# T4p1.net
KiCad netlist of a schematic drawn in EAGLE
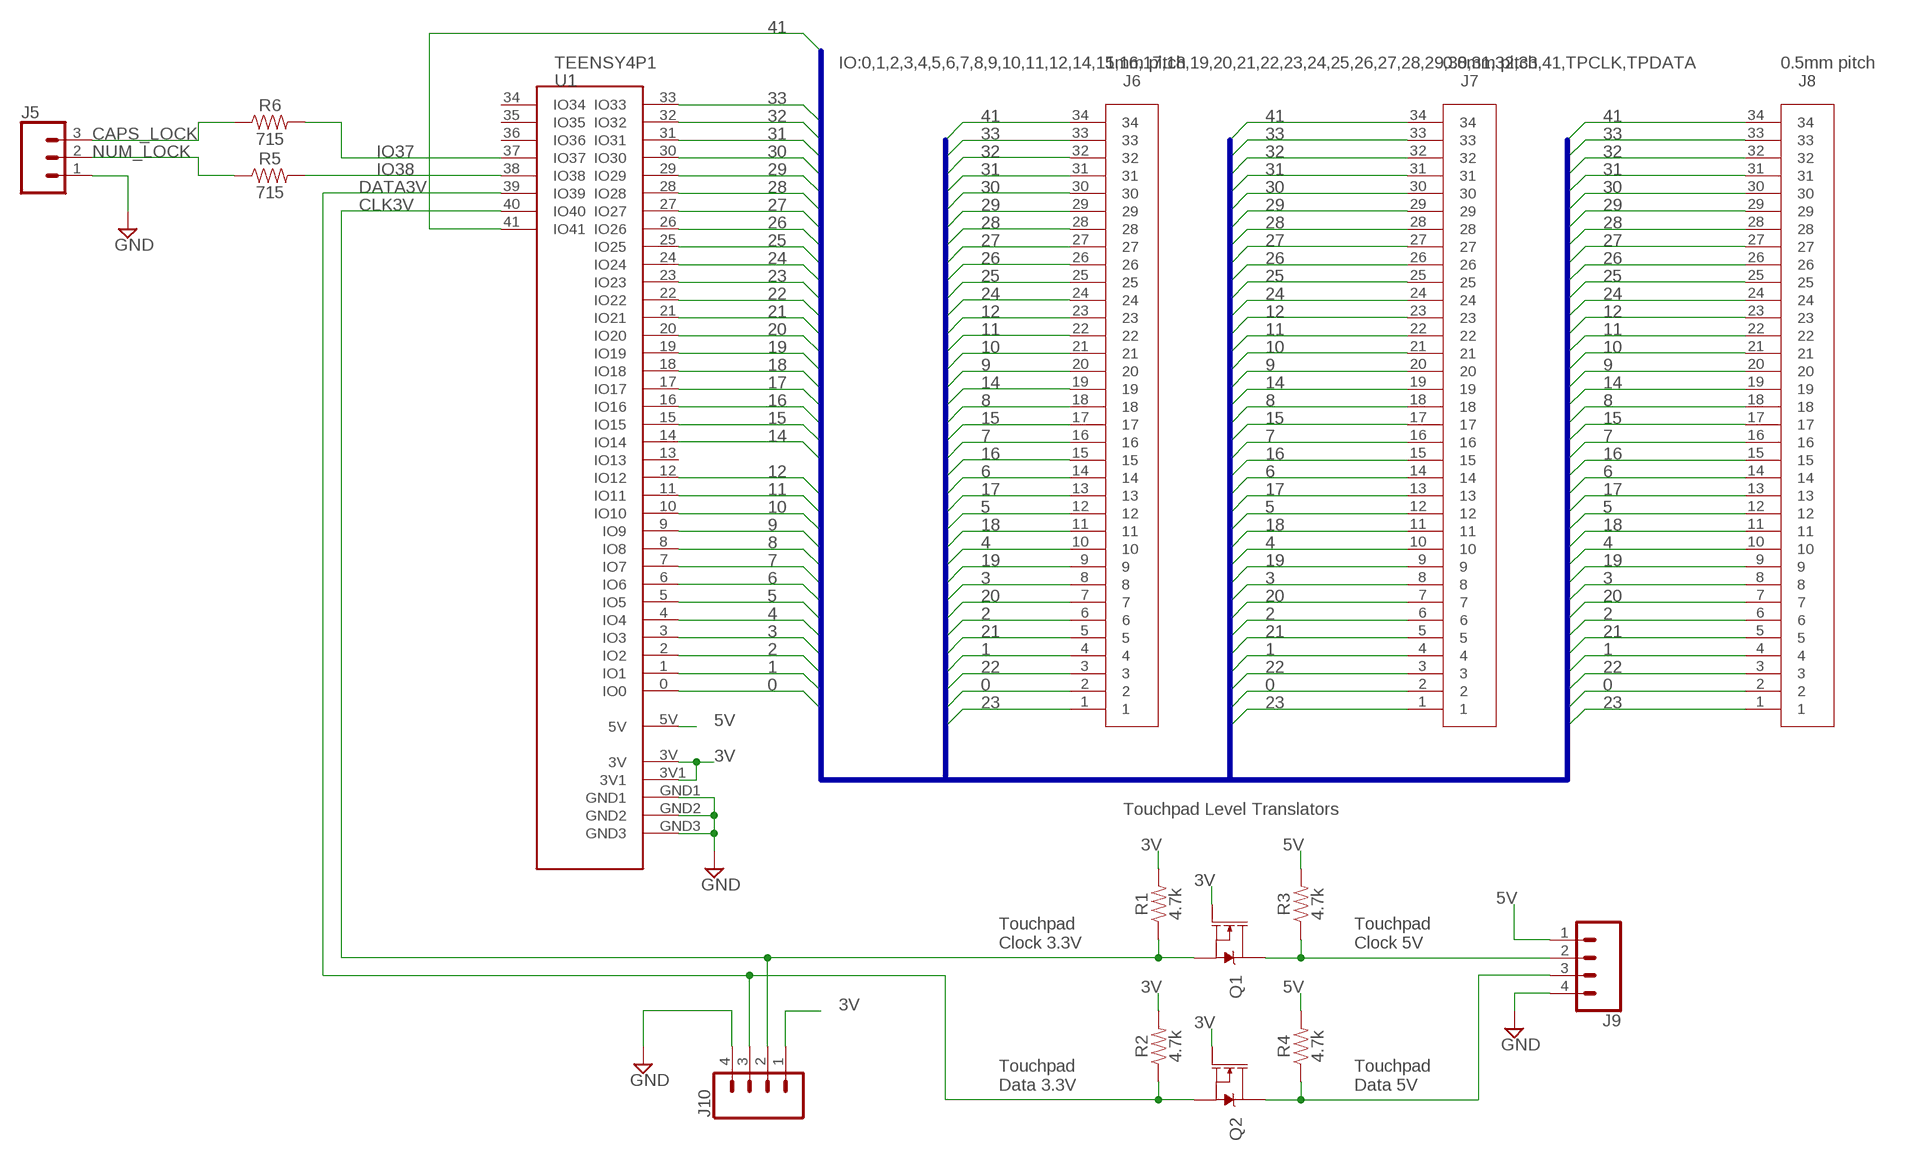
[diagram p0: schematic, sheet 1]

(export (version "E")
  (design (tool "Eeschema 10.0.6"))
  (components
    (comp (ref "J5")
      (value "CONN_031X03_NO_SILK")
      (footprint "eagle-import:1X03_NO_SILK")
      (libsource (lib "eagle-import") (part "CONN_031X03_NO_SILK"))
    )
    (comp (ref "J6")
      (value "FPC34")
      (footprint "eagle-import:FPC34")
      (libsource (lib "eagle-import") (part "FPC34"))
    )
    (comp (ref "J7")
      (value "FPC34_P8MM")
      (footprint "eagle-import:FPC34_P8MM")
      (libsource (lib "eagle-import") (part "FPC34_P8MM"))
    )
    (comp (ref "J8")
      (value "FPC34_P5MM")
      (footprint "eagle-import:FPC34_P5MM")
      (libsource (lib "eagle-import") (part "FPC34_P5MM"))
    )
    (comp (ref "J9")
      (value "CONN_041X04_NO_SILK")
      (footprint "eagle-import:1X04_NO_SILK")
      (libsource (lib "eagle-import") (part "CONN_041X04_NO_SILK"))
    )
    (comp (ref "J10")
      (value "CONN_041X04_NO_SILK")
      (footprint "eagle-import:1X04_NO_SILK")
      (libsource (lib "eagle-import") (part "CONN_041X04_NO_SILK"))
    )
    (comp (ref "Q1")
      (value "220mA/50V/3.5Ω")
      (footprint "eagle-import:SOT23-3")
      (libsource (lib "eagle-import") (part "MOSFET-NCH-BSS138"))
    )
    (comp (ref "Q2")
      (value "220mA/50V/3.5Ω")
      (footprint "eagle-import:SOT23-3")
      (libsource (lib "eagle-import") (part "MOSFET-NCH-BSS138"))
    )
    (comp (ref "R1")
      (value "4.7k")
      (footprint "eagle-import:0603")
      (libsource (lib "eagle-import") (part "4.7KOHM-0603-1/10W-1%"))
    )
    (comp (ref "R2")
      (value "4.7k")
      (footprint "eagle-import:0603")
      (libsource (lib "eagle-import") (part "4.7KOHM-0603-1/10W-1%"))
    )
    (comp (ref "R3")
      (value "4.7k")
      (footprint "eagle-import:0603")
      (libsource (lib "eagle-import") (part "4.7KOHM-0603-1/10W-1%"))
    )
    (comp (ref "R4")
      (value "4.7k")
      (footprint "eagle-import:0603")
      (libsource (lib "eagle-import") (part "4.7KOHM-0603-1/10W-1%"))
    )
    (comp (ref "R5")
      (value "715")
      (footprint "eagle-import:0603")
      (libsource (lib "eagle-import") (part "715OHM-0603-1/10W-1%"))
    )
    (comp (ref "R6")
      (value "715")
      (footprint "eagle-import:0603")
      (libsource (lib "eagle-import") (part "715OHM-0603-1/10W-1%"))
    )
    (comp (ref "U1")
      (value "TEENSY4P1")
      (footprint "eagle-import:TEENSY4P1")
      (libsource (lib "eagle-import") (part "TEENSYP41"))
    )
  )
  (nets
    (net (code "4") (name "/0") (class "Default")
      (node (ref "J6") (pin "2") (pinfunction "2_2") (pintype "bidirectional"))
      (node (ref "J7") (pin "2") (pinfunction "2_2") (pintype "bidirectional"))
      (node (ref "J8") (pin "2") (pinfunction "2_2") (pintype "bidirectional"))
      (node (ref "U1") (pin "0") (pinfunction "IO0_0") (pintype "bidirectional"))
    )
    (net (code "5") (name "/1") (class "Default")
      (node (ref "J6") (pin "4") (pinfunction "4_4") (pintype "bidirectional"))
      (node (ref "J7") (pin "4") (pinfunction "4_4") (pintype "bidirectional"))
      (node (ref "J8") (pin "4") (pinfunction "4_4") (pintype "bidirectional"))
      (node (ref "U1") (pin "1") (pinfunction "IO1_1") (pintype "bidirectional"))
    )
    (net (code "6") (name "/2") (class "Default")
      (node (ref "J6") (pin "6") (pinfunction "6_6") (pintype "bidirectional"))
      (node (ref "J7") (pin "6") (pinfunction "6_6") (pintype "bidirectional"))
      (node (ref "J8") (pin "6") (pinfunction "6_6") (pintype "bidirectional"))
      (node (ref "U1") (pin "2") (pinfunction "IO2_2") (pintype "bidirectional"))
    )
    (net (code "7") (name "/3") (class "Default")
      (node (ref "J6") (pin "8") (pinfunction "8_8") (pintype "bidirectional"))
      (node (ref "J7") (pin "8") (pinfunction "8_8") (pintype "bidirectional"))
      (node (ref "J8") (pin "8") (pinfunction "8_8") (pintype "bidirectional"))
      (node (ref "U1") (pin "3") (pinfunction "IO3_3") (pintype "bidirectional"))
    )
    (net (code "8") (name "/3V") (class "Default")
      (node (ref "J10") (pin "1") (pinfunction "1_1") (pintype "passive"))
      (node (ref "Q1") (pin "1") (pinfunction "G_1") (pintype "bidirectional"))
      (node (ref "Q2") (pin "1") (pinfunction "G_1") (pintype "bidirectional"))
      (node (ref "R1") (pin "2") (pinfunction "2_2") (pintype "passive"))
      (node (ref "R2") (pin "2") (pinfunction "2_2") (pintype "passive"))
      (node (ref "U1") (pin "3V") (pinfunction "3V_3V") (pintype "bidirectional"))
      (node (ref "U1") (pin "3V1") (pinfunction "3V1_3V1") (pintype "bidirectional"))
    )
    (net (code "9") (name "/4") (class "Default")
      (node (ref "J6") (pin "10") (pinfunction "10_10") (pintype "bidirectional"))
      (node (ref "J7") (pin "10") (pinfunction "10_10") (pintype "bidirectional"))
      (node (ref "J8") (pin "10") (pinfunction "10_10") (pintype "bidirectional"))
      (node (ref "U1") (pin "4") (pinfunction "IO4_4") (pintype "bidirectional"))
    )
    (net (code "10") (name "/5") (class "Default")
      (node (ref "J6") (pin "12") (pinfunction "12_12") (pintype "bidirectional"))
      (node (ref "J7") (pin "12") (pinfunction "12_12") (pintype "bidirectional"))
      (node (ref "J8") (pin "12") (pinfunction "12_12") (pintype "bidirectional"))
      (node (ref "U1") (pin "5") (pinfunction "IO5_5") (pintype "bidirectional"))
    )
    (net (code "11") (name "/5V") (class "Default")
      (node (ref "J9") (pin "1") (pinfunction "1_1") (pintype "passive"))
      (node (ref "R3") (pin "2") (pinfunction "2_2") (pintype "passive"))
      (node (ref "R4") (pin "2") (pinfunction "2_2") (pintype "passive"))
      (node (ref "U1") (pin "5V") (pinfunction "5V_5V") (pintype "bidirectional"))
    )
    (net (code "12") (name "/6") (class "Default")
      (node (ref "J6") (pin "14") (pinfunction "14_14") (pintype "bidirectional"))
      (node (ref "J7") (pin "14") (pinfunction "14_14") (pintype "bidirectional"))
      (node (ref "J8") (pin "14") (pinfunction "14_14") (pintype "bidirectional"))
      (node (ref "U1") (pin "6") (pinfunction "IO6_6") (pintype "bidirectional"))
    )
    (net (code "13") (name "/7") (class "Default")
      (node (ref "J6") (pin "16") (pinfunction "16_16") (pintype "bidirectional"))
      (node (ref "J7") (pin "16") (pinfunction "16_16") (pintype "bidirectional"))
      (node (ref "J8") (pin "16") (pinfunction "16_16") (pintype "bidirectional"))
      (node (ref "U1") (pin "7") (pinfunction "IO7_7") (pintype "bidirectional"))
    )
    (net (code "14") (name "/8") (class "Default")
      (node (ref "J6") (pin "18") (pinfunction "18_18") (pintype "bidirectional"))
      (node (ref "J7") (pin "18") (pinfunction "18_18") (pintype "bidirectional"))
      (node (ref "J8") (pin "18") (pinfunction "18_18") (pintype "bidirectional"))
      (node (ref "U1") (pin "8") (pinfunction "IO8_8") (pintype "bidirectional"))
    )
    (net (code "15") (name "/9") (class "Default")
      (node (ref "J6") (pin "20") (pinfunction "20_20") (pintype "bidirectional"))
      (node (ref "J7") (pin "20") (pinfunction "20_20") (pintype "bidirectional"))
      (node (ref "J8") (pin "20") (pinfunction "20_20") (pintype "bidirectional"))
      (node (ref "U1") (pin "9") (pinfunction "IO9_9") (pintype "bidirectional"))
    )
    (net (code "16") (name "/10") (class "Default")
      (node (ref "J6") (pin "21") (pinfunction "21_21") (pintype "bidirectional"))
      (node (ref "J7") (pin "21") (pinfunction "21_21") (pintype "bidirectional"))
      (node (ref "J8") (pin "21") (pinfunction "21_21") (pintype "bidirectional"))
      (node (ref "U1") (pin "10") (pinfunction "IO10_10") (pintype "bidirectional"))
    )
    (net (code "17") (name "/11") (class "Default")
      (node (ref "J6") (pin "22") (pinfunction "22_22") (pintype "bidirectional"))
      (node (ref "J7") (pin "22") (pinfunction "22_22") (pintype "bidirectional"))
      (node (ref "J8") (pin "22") (pinfunction "22_22") (pintype "bidirectional"))
      (node (ref "U1") (pin "11") (pinfunction "IO11_11") (pintype "bidirectional"))
    )
    (net (code "18") (name "/12") (class "Default")
      (node (ref "J6") (pin "23") (pinfunction "23_23") (pintype "bidirectional"))
      (node (ref "J7") (pin "23") (pinfunction "23_23") (pintype "bidirectional"))
      (node (ref "J8") (pin "23") (pinfunction "23_23") (pintype "bidirectional"))
      (node (ref "U1") (pin "12") (pinfunction "IO12_12") (pintype "bidirectional"))
    )
    (net (code "19") (name "/14") (class "Default")
      (node (ref "J6") (pin "19") (pinfunction "19_19") (pintype "bidirectional"))
      (node (ref "J7") (pin "19") (pinfunction "19_19") (pintype "bidirectional"))
      (node (ref "J8") (pin "19") (pinfunction "19_19") (pintype "bidirectional"))
      (node (ref "U1") (pin "14") (pinfunction "IO14_14") (pintype "bidirectional"))
    )
    (net (code "20") (name "/15") (class "Default")
      (node (ref "J6") (pin "17") (pinfunction "17_17") (pintype "bidirectional"))
      (node (ref "J7") (pin "17") (pinfunction "17_17") (pintype "bidirectional"))
      (node (ref "J8") (pin "17") (pinfunction "17_17") (pintype "bidirectional"))
      (node (ref "U1") (pin "15") (pinfunction "IO15_15") (pintype "bidirectional"))
    )
    (net (code "21") (name "/16") (class "Default")
      (node (ref "J6") (pin "15") (pinfunction "15_15") (pintype "bidirectional"))
      (node (ref "J7") (pin "15") (pinfunction "15_15") (pintype "bidirectional"))
      (node (ref "J8") (pin "15") (pinfunction "15_15") (pintype "bidirectional"))
      (node (ref "U1") (pin "16") (pinfunction "IO16_16") (pintype "bidirectional"))
    )
    (net (code "22") (name "/17") (class "Default")
      (node (ref "J6") (pin "13") (pinfunction "13_13") (pintype "bidirectional"))
      (node (ref "J7") (pin "13") (pinfunction "13_13") (pintype "bidirectional"))
      (node (ref "J8") (pin "13") (pinfunction "13_13") (pintype "bidirectional"))
      (node (ref "U1") (pin "17") (pinfunction "IO17_17") (pintype "bidirectional"))
    )
    (net (code "23") (name "/18") (class "Default")
      (node (ref "J6") (pin "11") (pinfunction "11_11") (pintype "bidirectional"))
      (node (ref "J7") (pin "11") (pinfunction "11_11") (pintype "bidirectional"))
      (node (ref "J8") (pin "11") (pinfunction "11_11") (pintype "bidirectional"))
      (node (ref "U1") (pin "18") (pinfunction "IO18_18") (pintype "bidirectional"))
    )
    (net (code "24") (name "/19") (class "Default")
      (node (ref "J6") (pin "9") (pinfunction "9_9") (pintype "bidirectional"))
      (node (ref "J7") (pin "9") (pinfunction "9_9") (pintype "bidirectional"))
      (node (ref "J8") (pin "9") (pinfunction "9_9") (pintype "bidirectional"))
      (node (ref "U1") (pin "19") (pinfunction "IO19_19") (pintype "bidirectional"))
    )
    (net (code "25") (name "/20") (class "Default")
      (node (ref "J6") (pin "7") (pinfunction "7_7") (pintype "bidirectional"))
      (node (ref "J7") (pin "7") (pinfunction "7_7") (pintype "bidirectional"))
      (node (ref "J8") (pin "7") (pinfunction "7_7") (pintype "bidirectional"))
      (node (ref "U1") (pin "20") (pinfunction "IO20_20") (pintype "bidirectional"))
    )
    (net (code "26") (name "/21") (class "Default")
      (node (ref "J6") (pin "5") (pinfunction "5_5") (pintype "bidirectional"))
      (node (ref "J7") (pin "5") (pinfunction "5_5") (pintype "bidirectional"))
      (node (ref "J8") (pin "5") (pinfunction "5_5") (pintype "bidirectional"))
      (node (ref "U1") (pin "21") (pinfunction "IO21_21") (pintype "bidirectional"))
    )
    (net (code "27") (name "/22") (class "Default")
      (node (ref "J6") (pin "3") (pinfunction "3_3") (pintype "bidirectional"))
      (node (ref "J7") (pin "3") (pinfunction "3_3") (pintype "bidirectional"))
      (node (ref "J8") (pin "3") (pinfunction "3_3") (pintype "bidirectional"))
      (node (ref "U1") (pin "22") (pinfunction "IO22_22") (pintype "bidirectional"))
    )
    (net (code "28") (name "/23") (class "Default")
      (node (ref "J6") (pin "1") (pinfunction "1_1") (pintype "bidirectional"))
      (node (ref "J7") (pin "1") (pinfunction "1_1") (pintype "bidirectional"))
      (node (ref "J8") (pin "1") (pinfunction "1_1") (pintype "bidirectional"))
      (node (ref "U1") (pin "23") (pinfunction "IO23_23") (pintype "bidirectional"))
    )
    (net (code "29") (name "/24") (class "Default")
      (node (ref "J6") (pin "24") (pinfunction "24_24") (pintype "bidirectional"))
      (node (ref "J7") (pin "24") (pinfunction "24_24") (pintype "bidirectional"))
      (node (ref "J8") (pin "24") (pinfunction "24_24") (pintype "bidirectional"))
      (node (ref "U1") (pin "24") (pinfunction "IO24_24") (pintype "bidirectional"))
    )
    (net (code "30") (name "/25") (class "Default")
      (node (ref "J6") (pin "25") (pinfunction "25_25") (pintype "bidirectional"))
      (node (ref "J7") (pin "25") (pinfunction "25_25") (pintype "bidirectional"))
      (node (ref "J8") (pin "25") (pinfunction "25_25") (pintype "bidirectional"))
      (node (ref "U1") (pin "25") (pinfunction "IO25_25") (pintype "bidirectional"))
    )
    (net (code "31") (name "/26") (class "Default")
      (node (ref "J6") (pin "26") (pinfunction "26_26") (pintype "bidirectional"))
      (node (ref "J7") (pin "26") (pinfunction "26_26") (pintype "bidirectional"))
      (node (ref "J8") (pin "26") (pinfunction "26_26") (pintype "bidirectional"))
      (node (ref "U1") (pin "26") (pinfunction "IO26_26") (pintype "bidirectional"))
    )
    (net (code "32") (name "/27") (class "Default")
      (node (ref "J6") (pin "27") (pinfunction "27_27") (pintype "bidirectional"))
      (node (ref "J7") (pin "27") (pinfunction "27_27") (pintype "bidirectional"))
      (node (ref "J8") (pin "27") (pinfunction "27_27") (pintype "bidirectional"))
      (node (ref "U1") (pin "27") (pinfunction "IO27_27") (pintype "bidirectional"))
    )
    (net (code "33") (name "/28") (class "Default")
      (node (ref "J6") (pin "28") (pinfunction "28_28") (pintype "bidirectional"))
      (node (ref "J7") (pin "28") (pinfunction "28_28") (pintype "bidirectional"))
      (node (ref "J8") (pin "28") (pinfunction "28_28") (pintype "bidirectional"))
      (node (ref "U1") (pin "28") (pinfunction "IO28_28") (pintype "bidirectional"))
    )
    (net (code "34") (name "/29") (class "Default")
      (node (ref "J6") (pin "29") (pinfunction "29_29") (pintype "bidirectional"))
      (node (ref "J7") (pin "29") (pinfunction "29_29") (pintype "bidirectional"))
      (node (ref "J8") (pin "29") (pinfunction "29_29") (pintype "bidirectional"))
      (node (ref "U1") (pin "29") (pinfunction "IO29_29") (pintype "bidirectional"))
    )
    (net (code "35") (name "/30") (class "Default")
      (node (ref "J6") (pin "30") (pinfunction "30_30") (pintype "bidirectional"))
      (node (ref "J7") (pin "30") (pinfunction "30_30") (pintype "bidirectional"))
      (node (ref "J8") (pin "30") (pinfunction "30_30") (pintype "bidirectional"))
      (node (ref "U1") (pin "30") (pinfunction "IO30_30") (pintype "bidirectional"))
    )
    (net (code "36") (name "/31") (class "Default")
      (node (ref "J6") (pin "31") (pinfunction "31_31") (pintype "bidirectional"))
      (node (ref "J7") (pin "31") (pinfunction "31_31") (pintype "bidirectional"))
      (node (ref "J8") (pin "31") (pinfunction "31_31") (pintype "bidirectional"))
      (node (ref "U1") (pin "31") (pinfunction "IO31_31") (pintype "bidirectional"))
    )
    (net (code "37") (name "/32") (class "Default")
      (node (ref "J6") (pin "32") (pinfunction "32_32") (pintype "bidirectional"))
      (node (ref "J7") (pin "32") (pinfunction "32_32") (pintype "bidirectional"))
      (node (ref "J8") (pin "32") (pinfunction "32_32") (pintype "bidirectional"))
      (node (ref "U1") (pin "32") (pinfunction "IO32_32") (pintype "bidirectional"))
    )
    (net (code "38") (name "/33") (class "Default")
      (node (ref "J6") (pin "33") (pinfunction "33_33") (pintype "bidirectional"))
      (node (ref "J7") (pin "33") (pinfunction "33_33") (pintype "bidirectional"))
      (node (ref "J8") (pin "33") (pinfunction "33_33") (pintype "bidirectional"))
      (node (ref "U1") (pin "33") (pinfunction "IO33_33") (pintype "bidirectional"))
    )
    (net (code "39") (name "/41") (class "Default")
      (node (ref "J6") (pin "34") (pinfunction "34_34") (pintype "bidirectional"))
      (node (ref "J7") (pin "34") (pinfunction "34_34") (pintype "bidirectional"))
      (node (ref "J8") (pin "34") (pinfunction "34_34") (pintype "bidirectional"))
      (node (ref "U1") (pin "41") (pinfunction "IO41_41") (pintype "bidirectional"))
    )
    (net (code "40") (name "/CAPS_LOCK") (class "Default")
      (node (ref "J5") (pin "3") (pinfunction "3_3") (pintype "passive"))
      (node (ref "R6") (pin "1") (pinfunction "1_1") (pintype "passive"))
    )
    (net (code "41") (name "/CLK3V") (class "Default")
      (node (ref "J10") (pin "2") (pinfunction "2_2") (pintype "passive"))
      (node (ref "Q1") (pin "2") (pinfunction "S_2") (pintype "bidirectional"))
      (node (ref "R1") (pin "1") (pinfunction "1_1") (pintype "passive"))
      (node (ref "U1") (pin "40") (pinfunction "IO40_40") (pintype "bidirectional"))
    )
    (net (code "42") (name "/DATA3V") (class "Default")
      (node (ref "J10") (pin "3") (pinfunction "3_3") (pintype "passive"))
      (node (ref "Q2") (pin "2") (pinfunction "S_2") (pintype "bidirectional"))
      (node (ref "R2") (pin "1") (pinfunction "1_1") (pintype "passive"))
      (node (ref "U1") (pin "39") (pinfunction "IO39_39") (pintype "bidirectional"))
    )
    (net (code "43") (name "/IO37") (class "Default")
      (node (ref "R6") (pin "2") (pinfunction "2_2") (pintype "passive"))
      (node (ref "U1") (pin "37") (pinfunction "IO37_37") (pintype "bidirectional"))
    )
    (net (code "44") (name "/IO38") (class "Default")
      (node (ref "R5") (pin "2") (pinfunction "2_2") (pintype "passive"))
      (node (ref "U1") (pin "38") (pinfunction "IO38_38") (pintype "bidirectional"))
    )
    (net (code "45") (name "/NUM_LOCK") (class "Default")
      (node (ref "J5") (pin "2") (pinfunction "2_2") (pintype "passive"))
      (node (ref "R5") (pin "1") (pinfunction "1_1") (pintype "passive"))
    )
    (net (code "47") (name "GND") (class "Default")
      (node (ref "J10") (pin "4") (pinfunction "4_4") (pintype "passive"))
      (node (ref "J5") (pin "1") (pinfunction "1_1") (pintype "passive"))
      (node (ref "J9") (pin "4") (pinfunction "4_4") (pintype "passive"))
      (node (ref "U1") (pin "GND1") (pinfunction "GND1_GND1") (pintype "bidirectional"))
      (node (ref "U1") (pin "GND2") (pinfunction "GND2_GND2") (pintype "bidirectional"))
      (node (ref "U1") (pin "GND3") (pinfunction "GND3_GND3") (pintype "bidirectional"))
    )
    (net (code "48") (name "Net-(Q1-D)") (class "Default")
      (node (ref "J9") (pin "2") (pinfunction "2_2") (pintype "passive"))
      (node (ref "Q1") (pin "3") (pinfunction "D_3") (pintype "bidirectional"))
      (node (ref "R3") (pin "1") (pinfunction "1_1") (pintype "passive"))
    )
    (net (code "49") (name "Net-(Q2-D)") (class "Default")
      (node (ref "J9") (pin "3") (pinfunction "3_3") (pintype "passive"))
      (node (ref "Q2") (pin "3") (pinfunction "D_3") (pintype "bidirectional"))
      (node (ref "R4") (pin "1") (pinfunction "1_1") (pintype "passive"))
    )
    (net (code "50") (name "unconnected-(U1-IO13-Pad13)") (class "Default")
      (node (ref "U1") (pin "13") (pinfunction "IO13_13") (pintype "bidirectional"))
    )
    (net (code "51") (name "unconnected-(U1-IO34-Pad34)") (class "Default")
      (node (ref "U1") (pin "34") (pinfunction "IO34_34") (pintype "bidirectional"))
    )
    (net (code "52") (name "unconnected-(U1-IO35-Pad35)") (class "Default")
      (node (ref "U1") (pin "35") (pinfunction "IO35_35") (pintype "bidirectional"))
    )
    (net (code "53") (name "unconnected-(U1-IO36-Pad36)") (class "Default")
      (node (ref "U1") (pin "36") (pinfunction "IO36_36") (pintype "bidirectional"))
    )
  )
)
